# Round_Rev2.net
KiCad netlist of a schematic drawn in EAGLE
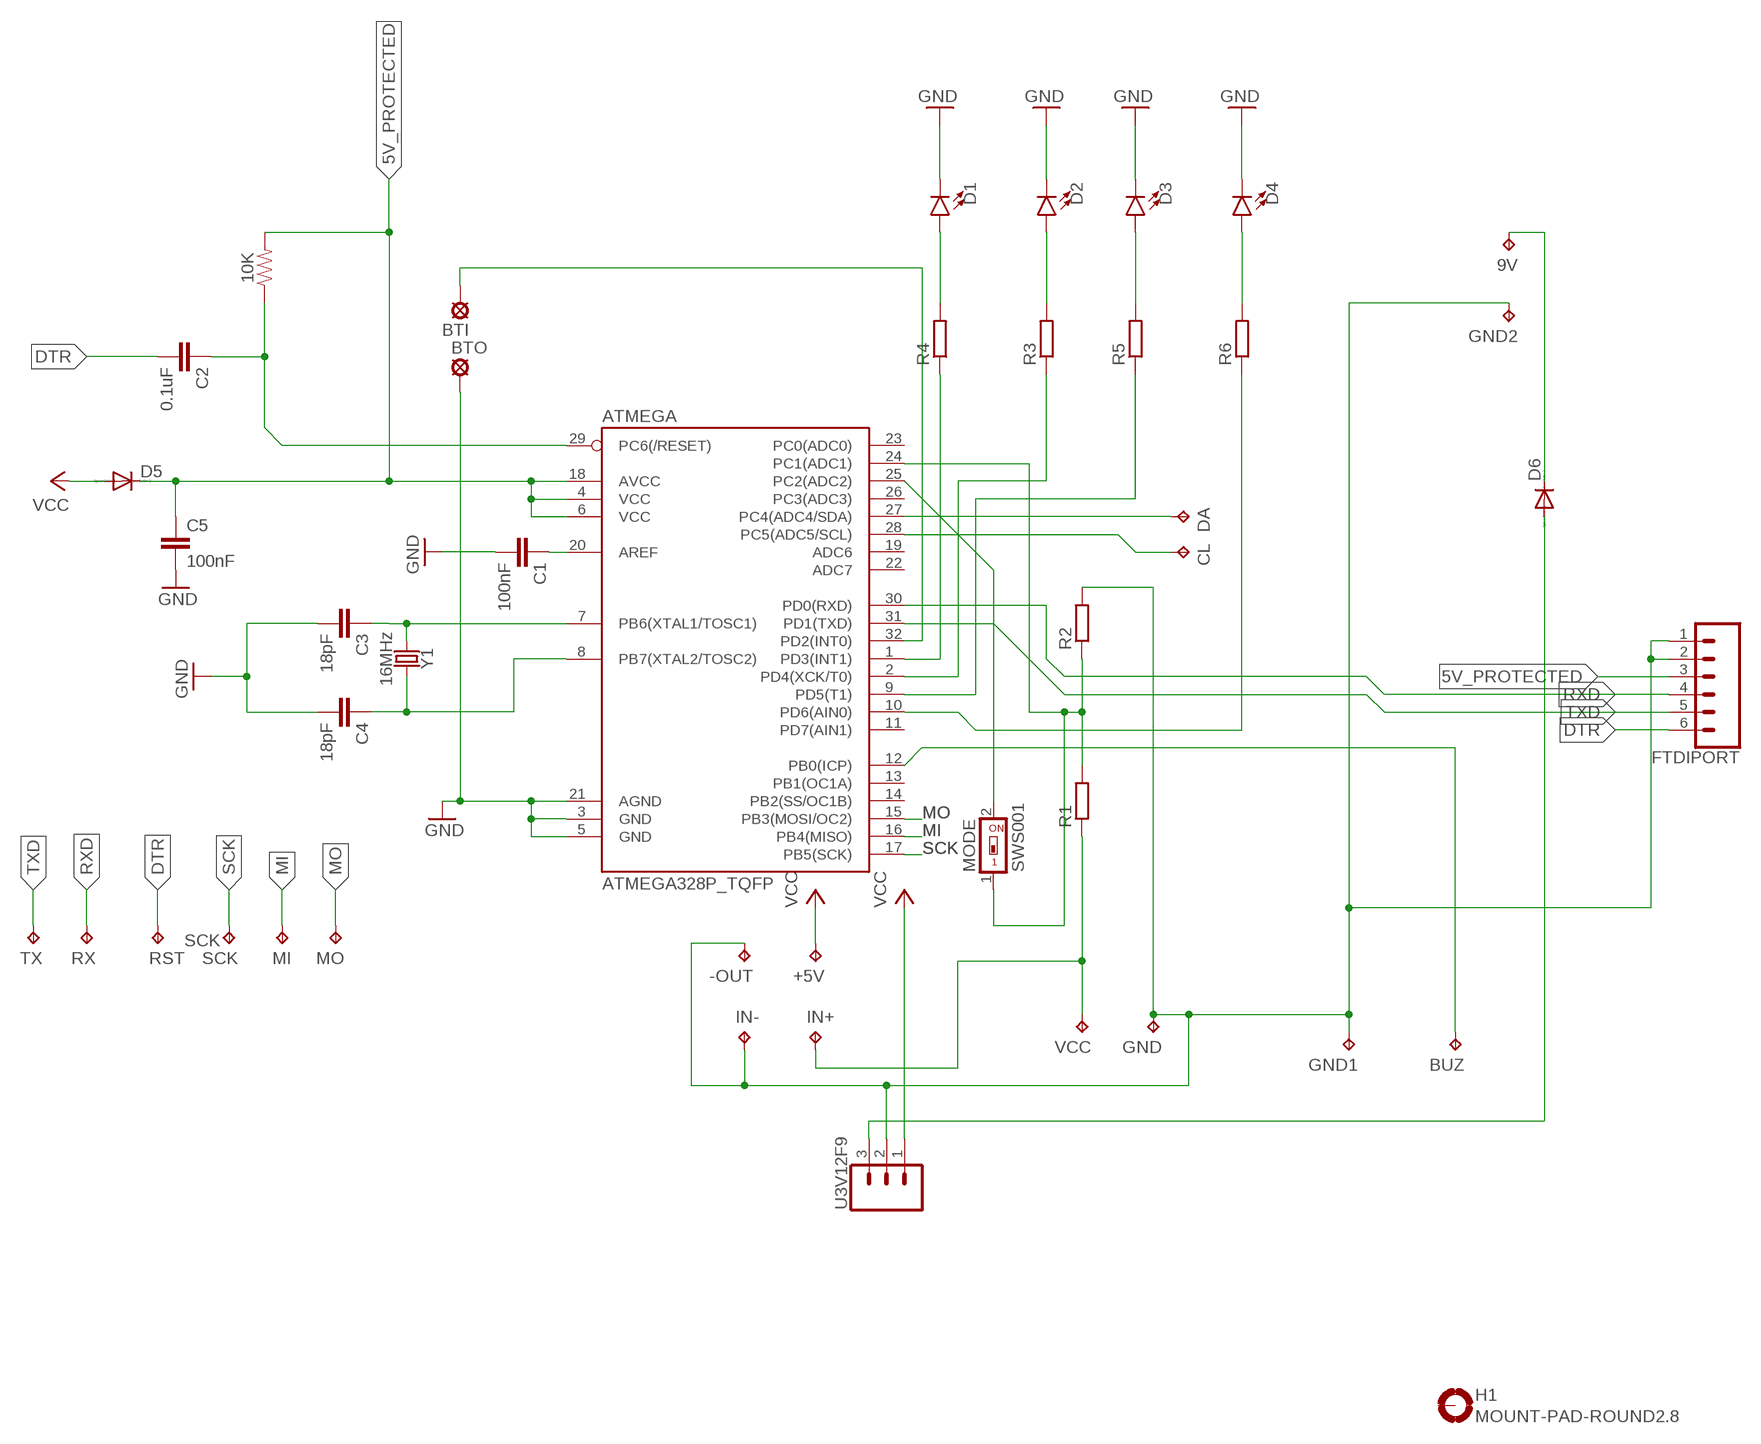
[diagram p0: schematic, sheet 1]

(export (version "E")
  (design (tool "Eeschema 10.0.6"))
  (components
    (comp (ref "+5V")
      (value "TPTP20SQ")
      (footprint "eagle-import:TP20SQ")
      (libsource (lib "eagle-import") (part "TPTP20SQ"))
    )
    (comp (ref "-OUT")
      (value "TPTP20SQ")
      (footprint "eagle-import:TP20SQ")
      (libsource (lib "eagle-import") (part "TPTP20SQ"))
    )
    (comp (ref "9V")
      (value "TPB2,54")
      (footprint "eagle-import:B2,54")
      (libsource (lib "eagle-import") (part "TPB2,54"))
    )
    (comp (ref "10K")
      (value "0.27OHM-0603-1/10W-1%")
      (footprint "eagle-import:0603")
      (libsource (lib "eagle-import") (part "0.27OHM-0603-1/10W-1%"))
    )
    (comp (ref "ATMEGA")
      (value "ATMEGA328P_TQFP")
      (footprint "eagle-import:TQFP32-08")
      (libsource (lib "eagle-import") (part "ATMEGA328P_TQFP"))
    )
    (comp (ref "BTI")
      (value "LSP10")
      (footprint "eagle-import:LSP10")
      (libsource (lib "eagle-import") (part "LSP10"))
    )
    (comp (ref "BTO")
      (value "LSP10")
      (footprint "eagle-import:LSP10")
      (libsource (lib "eagle-import") (part "LSP10"))
    )
    (comp (ref "BUZ")
      (value "TPB2,54")
      (footprint "eagle-import:B2,54")
      (libsource (lib "eagle-import") (part "TPB2,54"))
    )
    (comp (ref "C1")
      (value "100nF")
      (footprint "eagle-import:0603")
      (libsource (lib "eagle-import") (part "10NF-0603-50V-10%"))
    )
    (comp (ref "C2")
      (value "0.1uF")
      (footprint "eagle-import:0603")
      (libsource (lib "eagle-import") (part "10NF-0603-50V-10%"))
    )
    (comp (ref "C3")
      (value "18pF")
      (footprint "eagle-import:0603")
      (libsource (lib "eagle-import") (part "10NF-0603-50V-10%"))
    )
    (comp (ref "C4")
      (value "18pF")
      (footprint "eagle-import:0603")
      (libsource (lib "eagle-import") (part "10NF-0603-50V-10%"))
    )
    (comp (ref "C5")
      (value "100nF")
      (footprint "eagle-import:0603")
      (libsource (lib "eagle-import") (part "10NF-0603-50V-10%"))
    )
    (comp (ref "CL")
      (value "TPB1,27")
      (footprint "eagle-import:B1,27")
      (libsource (lib "eagle-import") (part "TPB1,27"))
    )
    (comp (ref "D1")
      (value "LED1206")
      (footprint "eagle-import:LED-1206")
      (libsource (lib "eagle-import") (part "LED1206"))
    )
    (comp (ref "D2")
      (value "LED1206")
      (footprint "eagle-import:LED-1206")
      (libsource (lib "eagle-import") (part "LED1206"))
    )
    (comp (ref "D3")
      (value "LED1206")
      (footprint "eagle-import:LED-1206")
      (libsource (lib "eagle-import") (part "LED1206"))
    )
    (comp (ref "D4")
      (value "LED1206")
      (footprint "eagle-import:LED-1206")
      (libsource (lib "eagle-import") (part "LED1206"))
    )
    (comp (ref "D5")
      (value "DIODE-SOD106A-R")
      (footprint "eagle-import:SOD106A-R")
      (libsource (lib "eagle-import") (part "DIODE-SOD106A-R"))
    )
    (comp (ref "D6")
      (value "DIODE-SOD106A-R")
      (footprint "eagle-import:SOD106A-R")
      (libsource (lib "eagle-import") (part "DIODE-SOD106A-R"))
    )
    (comp (ref "DA")
      (value "TPB1,27")
      (footprint "eagle-import:B1,27")
      (libsource (lib "eagle-import") (part "TPB1,27"))
    )
    (comp (ref "FTDIPORT")
      (value "CONN_06SMD-1MM")
      (footprint "eagle-import:1X06-1MM")
      (libsource (lib "eagle-import") (part "CONN_06SMD-1MM"))
    )
    (comp (ref "GND")
      (value "TPB2,54")
      (footprint "eagle-import:B2,54")
      (libsource (lib "eagle-import") (part "TPB2,54"))
    )
    (comp (ref "GND1")
      (value "TPB2,54")
      (footprint "eagle-import:B2,54")
      (libsource (lib "eagle-import") (part "TPB2,54"))
    )
    (comp (ref "GND2")
      (value "TPB2,54")
      (footprint "eagle-import:B2,54")
      (libsource (lib "eagle-import") (part "TPB2,54"))
    )
    (comp (ref "H1")
      (value "MOUNT-PAD-ROUND2.8")
      (footprint "eagle-import:2,8-PAD")
      (libsource (lib "eagle-import") (part "MOUNT-PAD-ROUND2.8"))
    )
    (comp (ref "IN+")
      (value "TPTP20SQ")
      (footprint "eagle-import:TP20SQ")
      (libsource (lib "eagle-import") (part "TPTP20SQ"))
    )
    (comp (ref "IN-")
      (value "TPTP20SQ")
      (footprint "eagle-import:TP20SQ")
      (libsource (lib "eagle-import") (part "TPTP20SQ"))
    )
    (comp (ref "MI")
      (value "TPB1,27")
      (footprint "eagle-import:B1,27")
      (libsource (lib "eagle-import") (part "TPB1,27"))
    )
    (comp (ref "MO")
      (value "TPB1,27")
      (footprint "eagle-import:B1,27")
      (libsource (lib "eagle-import") (part "TPB1,27"))
    )
    (comp (ref "MODE")
      (value "SWS001")
      (footprint "eagle-import:SMS-001")
      (libsource (lib "eagle-import") (part "SWS001"))
    )
    (comp (ref "R1")
      (value "R-EU_R1206")
      (footprint "eagle-import:R1206")
      (libsource (lib "eagle-import") (part "R-EU_R1206"))
    )
    (comp (ref "R2")
      (value "R-EU_R1206")
      (footprint "eagle-import:R1206")
      (libsource (lib "eagle-import") (part "R-EU_R1206"))
    )
    (comp (ref "R3")
      (value "R-EU_R1206")
      (footprint "eagle-import:R1206")
      (libsource (lib "eagle-import") (part "R-EU_R1206"))
    )
    (comp (ref "R4")
      (value "R-EU_R1206")
      (footprint "eagle-import:R1206")
      (libsource (lib "eagle-import") (part "R-EU_R1206"))
    )
    (comp (ref "R5")
      (value "R-EU_R1206")
      (footprint "eagle-import:R1206")
      (libsource (lib "eagle-import") (part "R-EU_R1206"))
    )
    (comp (ref "R6")
      (value "R-EU_R1206")
      (footprint "eagle-import:R1206")
      (libsource (lib "eagle-import") (part "R-EU_R1206"))
    )
    (comp (ref "RST")
      (value "TPB1,27")
      (footprint "eagle-import:B1,27")
      (libsource (lib "eagle-import") (part "TPB1,27"))
    )
    (comp (ref "RX")
      (value "TPB1,27")
      (footprint "eagle-import:B1,27")
      (libsource (lib "eagle-import") (part "TPB1,27"))
    )
    (comp (ref "SCK")
      (value "TPB1,27")
      (footprint "eagle-import:B1,27")
      (fields (field (name "TP_SIGNAL_NAME") "SCK"))
      (libsource (lib "eagle-import") (part "TPB1,27"))
    )
    (comp (ref "TX")
      (value "TPB1,27")
      (footprint "eagle-import:B1,27")
      (libsource (lib "eagle-import") (part "TPB1,27"))
    )
    (comp (ref "U3V12F9")
      (value "CONN_03")
      (footprint "eagle-import:1X03")
      (libsource (lib "eagle-import") (part "CONN_03"))
    )
    (comp (ref "VCC")
      (value "TPB2,54")
      (footprint "eagle-import:B2,54")
      (libsource (lib "eagle-import") (part "TPB2,54"))
    )
    (comp (ref "Y1")
      (value "16MHz")
      (footprint "eagle-import:CRYSTAL-SMD-5X3.2-2PAD")
      (libsource (lib "eagle-import") (part "CRYSTALSMD-5X3.2-2PAD"))
    )
  )
  (nets
    (net (code "1") (name "5V_PROTECTED") (class "Default")
      (node (ref "10K") (pin "2") (pinfunction "2_2") (pintype "passive"))
      (node (ref "ATMEGA") (pin "18") (pinfunction "AVCC_18") (pintype "bidirectional"))
      (node (ref "ATMEGA") (pin "4") (pinfunction "VCC_4") (pintype "bidirectional"))
      (node (ref "ATMEGA") (pin "6") (pinfunction "VCC_6") (pintype "bidirectional"))
      (node (ref "C5") (pin "1") (pinfunction "1_1") (pintype "passive"))
      (node (ref "D5") (pin "C") (pinfunction "C_C") (pintype "passive"))
      (node (ref "FTDIPORT") (pin "3") (pinfunction "3_3") (pintype "passive"))
    )
    (net (code "2") (name "DTR") (class "Default")
      (node (ref "C2") (pin "2") (pinfunction "2_2") (pintype "passive"))
      (node (ref "FTDIPORT") (pin "6") (pinfunction "6_6") (pintype "passive"))
      (node (ref "RST") (pin "TP") (pinfunction "TP_TP") (pintype "input"))
    )
    (net (code "3") (name "GND") (class "Default")
      (node (ref "-OUT") (pin "TP") (pinfunction "TP_TP") (pintype "input"))
      (node (ref "ATMEGA") (pin "21") (pinfunction "AGND_21") (pintype "bidirectional"))
      (node (ref "ATMEGA") (pin "3") (pinfunction "GND_3") (pintype "bidirectional"))
      (node (ref "ATMEGA") (pin "5") (pinfunction "GND_5") (pintype "bidirectional"))
      (node (ref "BTO") (pin "MP") (pinfunction "MP_MP") (pintype "passive"))
      (node (ref "C1") (pin "2") (pinfunction "2_2") (pintype "passive"))
      (node (ref "C3") (pin "2") (pinfunction "2_2") (pintype "passive"))
      (node (ref "C4") (pin "2") (pinfunction "2_2") (pintype "passive"))
      (node (ref "C5") (pin "2") (pinfunction "2_2") (pintype "passive"))
      (node (ref "D1") (pin "C") (pinfunction "C_C") (pintype "passive"))
      (node (ref "D2") (pin "C") (pinfunction "C_C") (pintype "passive"))
      (node (ref "D3") (pin "C") (pinfunction "C_C") (pintype "passive"))
      (node (ref "D4") (pin "C") (pinfunction "C_C") (pintype "passive"))
      (node (ref "FTDIPORT") (pin "1") (pinfunction "1_1") (pintype "passive"))
      (node (ref "FTDIPORT") (pin "2") (pinfunction "2_2") (pintype "passive"))
      (node (ref "GND") (pin "TP") (pinfunction "TP_TP") (pintype "input"))
      (node (ref "GND1") (pin "TP") (pinfunction "TP_TP") (pintype "input"))
      (node (ref "GND2") (pin "TP") (pinfunction "TP_TP") (pintype "input"))
      (node (ref "IN-") (pin "TP") (pinfunction "TP_TP") (pintype "input"))
      (node (ref "R2") (pin "2") (pinfunction "2_2") (pintype "passive"))
      (node (ref "U3V12F9") (pin "2") (pinfunction "2_2") (pintype "passive"))
    )
    (net (code "4") (name "MI") (class "Default")
      (node (ref "ATMEGA") (pin "16") (pinfunction "PB4(MISO)_16") (pintype "bidirectional"))
      (node (ref "MI") (pin "TP") (pinfunction "TP_TP") (pintype "input"))
    )
    (net (code "5") (name "MO") (class "Default")
      (node (ref "ATMEGA") (pin "15") (pinfunction "PB3(MOSI/OC2)_15") (pintype "bidirectional"))
      (node (ref "MO") (pin "TP") (pinfunction "TP_TP") (pintype "input"))
    )
    (net (code "6") (name "Net-(9V-PadTP)") (class "Default")
      (node (ref "9V") (pin "TP") (pinfunction "TP_TP") (pintype "input"))
      (node (ref "D6") (pin "C") (pinfunction "C_C") (pintype "passive"))
    )
    (net (code "7") (name "Net-(ATMEGA-AREF)") (class "Default")
      (node (ref "ATMEGA") (pin "20") (pinfunction "AREF_20") (pintype "bidirectional"))
      (node (ref "C1") (pin "1") (pinfunction "1_1") (pintype "passive"))
    )
    (net (code "8") (name "Net-(ATMEGA-PB0(ICP))") (class "Default")
      (node (ref "ATMEGA") (pin "12") (pinfunction "PB0(ICP)_12") (pintype "bidirectional"))
      (node (ref "BUZ") (pin "TP") (pinfunction "TP_TP") (pintype "input"))
    )
    (net (code "9") (name "Net-(ATMEGA-PB6(XTAL1{slash}TOSC1))") (class "Default")
      (node (ref "ATMEGA") (pin "7") (pinfunction "PB6(XTAL1/TOSC1)_7") (pintype "bidirectional"))
      (node (ref "C3") (pin "1") (pinfunction "1_1") (pintype "passive"))
      (node (ref "Y1") (pin "P$1") (pinfunction "1_P$1") (pintype "passive"))
    )
    (net (code "10") (name "Net-(ATMEGA-PB7(XTAL2{slash}TOSC2))") (class "Default")
      (node (ref "ATMEGA") (pin "8") (pinfunction "PB7(XTAL2/TOSC2)_8") (pintype "bidirectional"))
      (node (ref "C4") (pin "1") (pinfunction "1_1") (pintype "passive"))
      (node (ref "Y1") (pin "P$2") (pinfunction "2_P$2") (pintype "passive"))
    )
    (net (code "11") (name "Net-(ATMEGA-PC1(ADC1))") (class "Default")
      (node (ref "ATMEGA") (pin "24") (pinfunction "PC1(ADC1)_24") (pintype "bidirectional"))
      (node (ref "MODE") (pin "1") (pinfunction "1_1") (pintype "passive"))
      (node (ref "R1") (pin "2") (pinfunction "2_2") (pintype "passive"))
      (node (ref "R2") (pin "1") (pinfunction "1_1") (pintype "passive"))
    )
    (net (code "12") (name "Net-(ATMEGA-PC2(ADC2))") (class "Default")
      (node (ref "ATMEGA") (pin "25") (pinfunction "PC2(ADC2)_25") (pintype "bidirectional"))
      (node (ref "MODE") (pin "2") (pinfunction "2_2") (pintype "passive"))
    )
    (net (code "13") (name "Net-(ATMEGA-PC4(ADC4{slash}SDA))") (class "Default")
      (node (ref "ATMEGA") (pin "27") (pinfunction "PC4(ADC4/SDA)_27") (pintype "bidirectional"))
      (node (ref "DA") (pin "TP") (pinfunction "TP_TP") (pintype "input"))
    )
    (net (code "14") (name "Net-(ATMEGA-PC5(ADC5{slash}SCL))") (class "Default")
      (node (ref "ATMEGA") (pin "28") (pinfunction "PC5(ADC5/SCL)_28") (pintype "bidirectional"))
      (node (ref "CL") (pin "TP") (pinfunction "TP_TP") (pintype "input"))
    )
    (net (code "15") (name "Net-(ATMEGA-PC6({slash}RESET))") (class "Default")
      (node (ref "10K") (pin "1") (pinfunction "1_1") (pintype "passive"))
      (node (ref "ATMEGA") (pin "29") (pinfunction "PC6(/RESET)_29") (pintype "bidirectional"))
      (node (ref "C2") (pin "1") (pinfunction "1_1") (pintype "passive"))
    )
    (net (code "16") (name "Net-(ATMEGA-PD2(INT0))") (class "Default")
      (node (ref "ATMEGA") (pin "32") (pinfunction "PD2(INT0)_32") (pintype "bidirectional"))
      (node (ref "BTI") (pin "MP") (pinfunction "MP_MP") (pintype "passive"))
    )
    (net (code "17") (name "Net-(ATMEGA-PD3(INT1))") (class "Default")
      (node (ref "ATMEGA") (pin "1") (pinfunction "PD3(INT1)_1") (pintype "bidirectional"))
      (node (ref "R4") (pin "1") (pinfunction "1_1") (pintype "passive"))
    )
    (net (code "18") (name "Net-(ATMEGA-PD4(XCK{slash}T0))") (class "Default")
      (node (ref "ATMEGA") (pin "2") (pinfunction "PD4(XCK/T0)_2") (pintype "bidirectional"))
      (node (ref "R3") (pin "1") (pinfunction "1_1") (pintype "passive"))
    )
    (net (code "19") (name "Net-(ATMEGA-PD5(T1))") (class "Default")
      (node (ref "ATMEGA") (pin "9") (pinfunction "PD5(T1)_9") (pintype "bidirectional"))
      (node (ref "R5") (pin "1") (pinfunction "1_1") (pintype "passive"))
    )
    (net (code "20") (name "Net-(ATMEGA-PD6(AIN0))") (class "Default")
      (node (ref "ATMEGA") (pin "10") (pinfunction "PD6(AIN0)_10") (pintype "bidirectional"))
      (node (ref "R6") (pin "1") (pinfunction "1_1") (pintype "passive"))
    )
    (net (code "21") (name "Net-(D1-PadA)") (class "Default")
      (node (ref "D1") (pin "A") (pinfunction "A_A") (pintype "passive"))
      (node (ref "R4") (pin "2") (pinfunction "2_2") (pintype "passive"))
    )
    (net (code "22") (name "Net-(D2-PadA)") (class "Default")
      (node (ref "D2") (pin "A") (pinfunction "A_A") (pintype "passive"))
      (node (ref "R3") (pin "2") (pinfunction "2_2") (pintype "passive"))
    )
    (net (code "23") (name "Net-(D3-PadA)") (class "Default")
      (node (ref "D3") (pin "A") (pinfunction "A_A") (pintype "passive"))
      (node (ref "R5") (pin "2") (pinfunction "2_2") (pintype "passive"))
    )
    (net (code "24") (name "Net-(D4-PadA)") (class "Default")
      (node (ref "D4") (pin "A") (pinfunction "A_A") (pintype "passive"))
      (node (ref "R6") (pin "2") (pinfunction "2_2") (pintype "passive"))
    )
    (net (code "25") (name "Net-(D6-PadA)") (class "Default")
      (node (ref "D6") (pin "A") (pinfunction "A_A") (pintype "passive"))
      (node (ref "U3V12F9") (pin "3") (pinfunction "3_3") (pintype "passive"))
    )
    (net (code "26") (name "RXD") (class "Default")
      (node (ref "ATMEGA") (pin "30") (pinfunction "PD0(RXD)_30") (pintype "bidirectional"))
      (node (ref "FTDIPORT") (pin "4") (pinfunction "4_4") (pintype "passive"))
      (node (ref "RX") (pin "TP") (pinfunction "TP_TP") (pintype "input"))
    )
    (net (code "27") (name "SCK") (class "Default")
      (node (ref "ATMEGA") (pin "17") (pinfunction "PB5(SCK)_17") (pintype "bidirectional"))
      (node (ref "SCK") (pin "TP") (pinfunction "TP_TP") (pintype "input"))
    )
    (net (code "28") (name "TXD") (class "Default")
      (node (ref "ATMEGA") (pin "31") (pinfunction "PD1(TXD)_31") (pintype "bidirectional"))
      (node (ref "FTDIPORT") (pin "5") (pinfunction "5_5") (pintype "passive"))
      (node (ref "TX") (pin "TP") (pinfunction "TP_TP") (pintype "input"))
    )
    (net (code "29") (name "VCC") (class "Default")
      (node (ref "+5V") (pin "TP") (pinfunction "TP_TP") (pintype "input"))
      (node (ref "D5") (pin "A") (pinfunction "A_A") (pintype "passive"))
      (node (ref "IN+") (pin "TP") (pinfunction "TP_TP") (pintype "input"))
      (node (ref "R1") (pin "1") (pinfunction "1_1") (pintype "passive"))
      (node (ref "U3V12F9") (pin "1") (pinfunction "1_1") (pintype "passive"))
      (node (ref "VCC") (pin "TP") (pinfunction "TP_TP") (pintype "input"))
    )
    (net (code "30") (name "unconnected-(ATMEGA-ADC6-Pad19)") (class "Default")
      (node (ref "ATMEGA") (pin "19") (pinfunction "ADC6_19") (pintype "bidirectional"))
    )
    (net (code "31") (name "unconnected-(ATMEGA-ADC7-Pad22)") (class "Default")
      (node (ref "ATMEGA") (pin "22") (pinfunction "ADC7_22") (pintype "bidirectional"))
    )
    (net (code "32") (name "unconnected-(ATMEGA-PB1(OC1A)-Pad13)") (class "Default")
      (node (ref "ATMEGA") (pin "13") (pinfunction "PB1(OC1A)_13") (pintype "bidirectional"))
    )
    (net (code "33") (name "unconnected-(ATMEGA-PB2(SS{slash}OC1B)-Pad14)") (class "Default")
      (node (ref "ATMEGA") (pin "14") (pinfunction "PB2(SS/OC1B)_14") (pintype "bidirectional"))
    )
    (net (code "34") (name "unconnected-(ATMEGA-PC0(ADC0)-Pad23)") (class "Default")
      (node (ref "ATMEGA") (pin "23") (pinfunction "PC0(ADC0)_23") (pintype "bidirectional"))
    )
    (net (code "35") (name "unconnected-(ATMEGA-PC3(ADC3)-Pad26)") (class "Default")
      (node (ref "ATMEGA") (pin "26") (pinfunction "PC3(ADC3)_26") (pintype "bidirectional"))
    )
    (net (code "36") (name "unconnected-(ATMEGA-PD7(AIN1)-Pad11)") (class "Default")
      (node (ref "ATMEGA") (pin "11") (pinfunction "PD7(AIN1)_11") (pintype "bidirectional"))
    )
    (net (code "37") (name "unconnected-(H1-MOUNT-PadB2,8)") (class "Default")
      (node (ref "H1") (pin "B2,8") (pinfunction "MOUNT_B2,8") (pintype "passive"))
    )
  )
)
